# sx1509-breakout.net
KiCad netlist of a schematic drawn in EAGLE
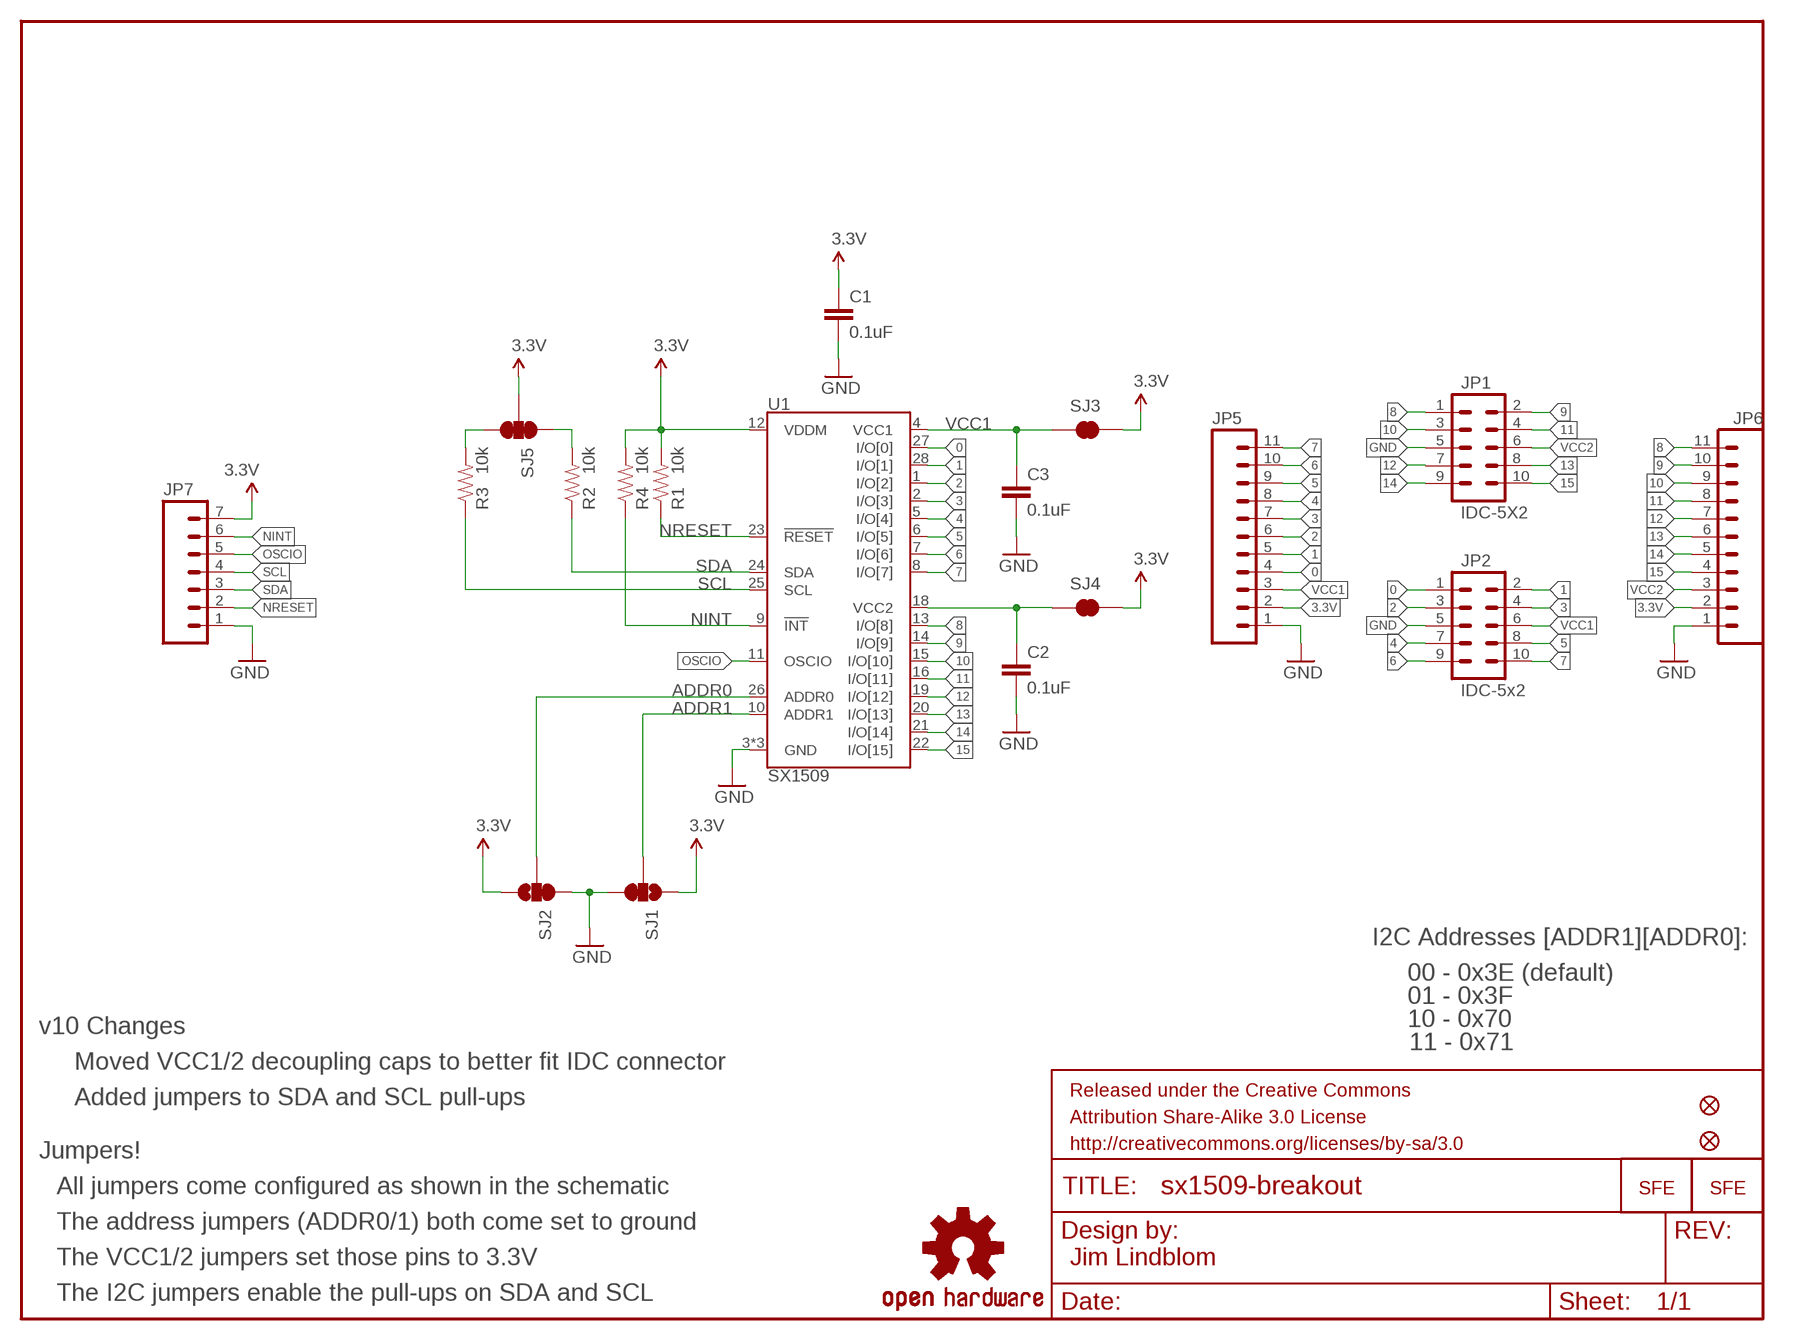
[diagram p0: schematic, sheet 1]

(export (version "E")
  (design (tool "Eeschema 10.0.6"))
  (components
    (comp (ref "C1")
      (value "0.1uF")
      (footprint "eagle-import:0402-CAP")
      (libsource (lib "eagle-import") (part "CAP0402-CAP"))
    )
    (comp (ref "C2")
      (value "0.1uF")
      (footprint "eagle-import:0402-CAP")
      (libsource (lib "eagle-import") (part "CAP0402-CAP"))
    )
    (comp (ref "C3")
      (value "0.1uF")
      (footprint "eagle-import:0402-CAP")
      (libsource (lib "eagle-import") (part "CAP0402-CAP"))
    )
    (comp (ref "JP1")
      (value "IDC-5X2")
      (footprint "eagle-import:2X5-SHROUDED-NO_SILK")
      (libsource (lib "eagle-import") (part "M05X2SHD_NS"))
    )
    (comp (ref "JP2")
      (value "IDC-5x2")
      (footprint "eagle-import:2X5-SHROUDED-NO_SILK")
      (libsource (lib "eagle-import") (part "M05X2SHD_NS"))
    )
    (comp (ref "JP3")
      (value "LOGO-SFENEW")
      (footprint "eagle-import:SFE-NEW-WEBLOGO")
      (libsource (lib "eagle-import") (part "LOGO-SFENEW"))
    )
    (comp (ref "JP4")
      (value "LOGO-SFESK")
      (footprint "eagle-import:SFE-LOGO-FLAME")
      (libsource (lib "eagle-import") (part "LOGO-SFESK"))
    )
    (comp (ref "JP5")
      (value "M111X11_NO_SILK")
      (footprint "eagle-import:1X11_NO_SILK")
      (libsource (lib "eagle-import") (part "M111X11_NO_SILK"))
    )
    (comp (ref "JP6")
      (value "M111X11_NO_SILK")
      (footprint "eagle-import:1X11_NO_SILK")
      (libsource (lib "eagle-import") (part "M111X11_NO_SILK"))
    )
    (comp (ref "JP7")
      (value "M07")
      (footprint "eagle-import:1X07")
      (libsource (lib "eagle-import") (part "M07"))
    )
    (comp (ref "JP8")
      (value "FIDUCIALUFIDUCIAL")
      (footprint "eagle-import:MICRO-FIDUCIAL")
      (libsource (lib "eagle-import") (part "FIDUCIALUFIDUCIAL"))
    )
    (comp (ref "JP9")
      (value "FIDUCIALUFIDUCIAL")
      (footprint "eagle-import:MICRO-FIDUCIAL")
      (libsource (lib "eagle-import") (part "FIDUCIALUFIDUCIAL"))
    )
    (comp (ref "R1")
      (value "10k")
      (footprint "eagle-import:0402-RES")
      (libsource (lib "eagle-import") (part "RESISTOR0402-RES"))
    )
    (comp (ref "R2")
      (value "10k")
      (footprint "eagle-import:0402-RES")
      (libsource (lib "eagle-import") (part "RESISTOR0402-RES"))
    )
    (comp (ref "R3")
      (value "10k")
      (footprint "eagle-import:0402-RES")
      (libsource (lib "eagle-import") (part "RESISTOR0402-RES"))
    )
    (comp (ref "R4")
      (value "10k")
      (footprint "eagle-import:0402-RES")
      (libsource (lib "eagle-import") (part "RESISTOR0402-RES"))
    )
    (comp (ref "SJ1")
      (value "SOLDERJUMPER_2WAYS")
      (footprint "eagle-import:SJ_3")
      (libsource (lib "eagle-import") (part "SOLDERJUMPER_2WAYS"))
    )
    (comp (ref "SJ2")
      (value "SOLDERJUMPER_2WAYS")
      (footprint "eagle-import:SJ_3")
      (libsource (lib "eagle-import") (part "SOLDERJUMPER_2WAYS"))
    )
    (comp (ref "SJ3")
      (value "SOLDERJUMPERNO")
      (footprint "eagle-import:SJ_2S-NO")
      (libsource (lib "eagle-import") (part "SOLDERJUMPERNO"))
    )
    (comp (ref "SJ4")
      (value "SOLDERJUMPERNO")
      (footprint "eagle-import:SJ_2S-NO")
      (libsource (lib "eagle-import") (part "SOLDERJUMPERNO"))
    )
    (comp (ref "SJ5")
      (value "SOLDERJUMPER_2WAYS")
      (footprint "eagle-import:SJ_3")
      (libsource (lib "eagle-import") (part "SOLDERJUMPER_2WAYS"))
    )
    (comp (ref "U$1")
      (value "OSHW-LOGOS")
      (footprint "eagle-import:OSHW-LOGO-S")
      (libsource (lib "eagle-import") (part "OSHW-LOGOS"))
    )
    (comp (ref "U1")
      (value "SX1509")
      (footprint "eagle-import:QFN-28")
      (libsource (lib "eagle-import") (part "SX1509"))
    )
  )
  (nets
    (net (code "1") (name "/ADDR0") (class "Default")
      (node (ref "SJ2") (pin "2") (pinfunction "2_2") (pintype "passive"))
      (node (ref "U1") (pin "26") (pinfunction "ADDR0_26") (pintype "bidirectional"))
    )
    (net (code "2") (name "/ADDR1") (class "Default")
      (node (ref "SJ1") (pin "2") (pinfunction "2_2") (pintype "passive"))
      (node (ref "U1") (pin "10") (pinfunction "ADDR1_10") (pintype "bidirectional"))
    )
    (net (code "3") (name "0") (class "Default")
      (node (ref "JP2") (pin "1") (pinfunction "1_1") (pintype "passive"))
      (node (ref "JP5") (pin "4") (pinfunction "4_4") (pintype "passive"))
      (node (ref "U1") (pin "27") (pinfunction "I/O[0]_27") (pintype "bidirectional"))
    )
    (net (code "4") (name "1") (class "Default")
      (node (ref "JP2") (pin "2") (pinfunction "2_2") (pintype "passive"))
      (node (ref "JP5") (pin "5") (pinfunction "5_5") (pintype "passive"))
      (node (ref "U1") (pin "28") (pinfunction "I/O[1]_28") (pintype "bidirectional"))
    )
    (net (code "5") (name "2") (class "Default")
      (node (ref "JP2") (pin "3") (pinfunction "3_3") (pintype "passive"))
      (node (ref "JP5") (pin "6") (pinfunction "6_6") (pintype "passive"))
      (node (ref "U1") (pin "1") (pinfunction "I/O[2]_1") (pintype "bidirectional"))
    )
    (net (code "6") (name "3") (class "Default")
      (node (ref "JP2") (pin "4") (pinfunction "4_4") (pintype "passive"))
      (node (ref "JP5") (pin "7") (pinfunction "7_7") (pintype "passive"))
      (node (ref "U1") (pin "2") (pinfunction "I/O[3]_2") (pintype "bidirectional"))
    )
    (net (code "7") (name "3.3V") (class "Default")
      (node (ref "C1") (pin "1") (pinfunction "1_1") (pintype "passive"))
      (node (ref "JP5") (pin "2") (pinfunction "2_2") (pintype "passive"))
      (node (ref "JP6") (pin "2") (pinfunction "2_2") (pintype "passive"))
      (node (ref "JP7") (pin "7") (pinfunction "7_7") (pintype "passive"))
      (node (ref "R1") (pin "2") (pinfunction "2_2") (pintype "passive"))
      (node (ref "R4") (pin "2") (pinfunction "2_2") (pintype "passive"))
      (node (ref "SJ1") (pin "1") (pinfunction "1_1") (pintype "passive"))
      (node (ref "SJ2") (pin "3") (pinfunction "3_3") (pintype "passive"))
      (node (ref "SJ3") (pin "2") (pinfunction "2_2") (pintype "passive"))
      (node (ref "SJ4") (pin "2") (pinfunction "2_2") (pintype "passive"))
      (node (ref "SJ5") (pin "2") (pinfunction "2_2") (pintype "passive"))
      (node (ref "U1") (pin "12") (pinfunction "VDDM_12") (pintype "bidirectional"))
    )
    (net (code "8") (name "4") (class "Default")
      (node (ref "JP2") (pin "7") (pinfunction "7_7") (pintype "passive"))
      (node (ref "JP5") (pin "8") (pinfunction "8_8") (pintype "passive"))
      (node (ref "U1") (pin "5") (pinfunction "I/O[4]_5") (pintype "bidirectional"))
    )
    (net (code "9") (name "5") (class "Default")
      (node (ref "JP2") (pin "8") (pinfunction "8_8") (pintype "passive"))
      (node (ref "JP5") (pin "9") (pinfunction "9_9") (pintype "passive"))
      (node (ref "U1") (pin "6") (pinfunction "I/O[5]_6") (pintype "bidirectional"))
    )
    (net (code "10") (name "6") (class "Default")
      (node (ref "JP2") (pin "9") (pinfunction "9_9") (pintype "passive"))
      (node (ref "JP5") (pin "10") (pinfunction "10_10") (pintype "passive"))
      (node (ref "U1") (pin "7") (pinfunction "I/O[6]_7") (pintype "bidirectional"))
    )
    (net (code "11") (name "7") (class "Default")
      (node (ref "JP2") (pin "10") (pinfunction "10_10") (pintype "passive"))
      (node (ref "JP5") (pin "11") (pinfunction "11_11") (pintype "passive"))
      (node (ref "U1") (pin "8") (pinfunction "I/O[7]_8") (pintype "bidirectional"))
    )
    (net (code "12") (name "8") (class "Default")
      (node (ref "JP1") (pin "1") (pinfunction "1_1") (pintype "passive"))
      (node (ref "JP6") (pin "11") (pinfunction "11_11") (pintype "passive"))
      (node (ref "U1") (pin "13") (pinfunction "I/O[8]_13") (pintype "bidirectional"))
    )
    (net (code "13") (name "9") (class "Default")
      (node (ref "JP1") (pin "2") (pinfunction "2_2") (pintype "passive"))
      (node (ref "JP6") (pin "10") (pinfunction "10_10") (pintype "passive"))
      (node (ref "U1") (pin "14") (pinfunction "I/O[9]_14") (pintype "bidirectional"))
    )
    (net (code "14") (name "10") (class "Default")
      (node (ref "JP1") (pin "3") (pinfunction "3_3") (pintype "passive"))
      (node (ref "JP6") (pin "9") (pinfunction "9_9") (pintype "passive"))
      (node (ref "U1") (pin "15") (pinfunction "I/O[10]_15") (pintype "bidirectional"))
    )
    (net (code "15") (name "11") (class "Default")
      (node (ref "JP1") (pin "4") (pinfunction "4_4") (pintype "passive"))
      (node (ref "JP6") (pin "8") (pinfunction "8_8") (pintype "passive"))
      (node (ref "U1") (pin "16") (pinfunction "I/O[11]_16") (pintype "bidirectional"))
    )
    (net (code "16") (name "12") (class "Default")
      (node (ref "JP1") (pin "7") (pinfunction "7_7") (pintype "passive"))
      (node (ref "JP6") (pin "7") (pinfunction "7_7") (pintype "passive"))
      (node (ref "U1") (pin "19") (pinfunction "I/O[12]_19") (pintype "bidirectional"))
    )
    (net (code "17") (name "13") (class "Default")
      (node (ref "JP1") (pin "8") (pinfunction "8_8") (pintype "passive"))
      (node (ref "JP6") (pin "6") (pinfunction "6_6") (pintype "passive"))
      (node (ref "U1") (pin "20") (pinfunction "I/O[13]_20") (pintype "bidirectional"))
    )
    (net (code "18") (name "14") (class "Default")
      (node (ref "JP1") (pin "9") (pinfunction "9_9") (pintype "passive"))
      (node (ref "JP6") (pin "5") (pinfunction "5_5") (pintype "passive"))
      (node (ref "U1") (pin "21") (pinfunction "I/O[14]_21") (pintype "bidirectional"))
    )
    (net (code "19") (name "15") (class "Default")
      (node (ref "JP1") (pin "10") (pinfunction "10_10") (pintype "passive"))
      (node (ref "JP6") (pin "4") (pinfunction "4_4") (pintype "passive"))
      (node (ref "U1") (pin "22") (pinfunction "I/O[15]_22") (pintype "bidirectional"))
    )
    (net (code "20") (name "GND") (class "Default")
      (node (ref "C1") (pin "2") (pinfunction "2_2") (pintype "passive"))
      (node (ref "C2") (pin "2") (pinfunction "2_2") (pintype "passive"))
      (node (ref "C3") (pin "2") (pinfunction "2_2") (pintype "passive"))
      (node (ref "JP1") (pin "5") (pinfunction "5_5") (pintype "passive"))
      (node (ref "JP2") (pin "5") (pinfunction "5_5") (pintype "passive"))
      (node (ref "JP5") (pin "1") (pinfunction "1_1") (pintype "passive"))
      (node (ref "JP6") (pin "1") (pinfunction "1_1") (pintype "passive"))
      (node (ref "JP7") (pin "1") (pinfunction "1_1") (pintype "passive"))
      (node (ref "SJ1") (pin "3") (pinfunction "3_3") (pintype "passive"))
      (node (ref "SJ2") (pin "1") (pinfunction "1_1") (pintype "passive"))
      (node (ref "U1") (pin "17") (pinfunction "GND_17") (pintype "bidirectional"))
      (node (ref "U1") (pin "29") (pinfunction "GND_29") (pintype "bidirectional"))
      (node (ref "U1") (pin "3") (pinfunction "GND_3") (pintype "bidirectional"))
    )
    (net (code "21") (name "NINT") (class "Default")
      (node (ref "JP7") (pin "6") (pinfunction "6_6") (pintype "passive"))
      (node (ref "R4") (pin "1") (pinfunction "1_1") (pintype "passive"))
      (node (ref "U1") (pin "9") (pinfunction "~{INT}_9") (pintype "bidirectional"))
    )
    (net (code "22") (name "NRESET") (class "Default")
      (node (ref "JP7") (pin "2") (pinfunction "2_2") (pintype "passive"))
      (node (ref "R1") (pin "1") (pinfunction "1_1") (pintype "passive"))
      (node (ref "U1") (pin "23") (pinfunction "~{RESET}_23") (pintype "bidirectional"))
    )
    (net (code "23") (name "Net-(R2-Pad2)") (class "Default")
      (node (ref "R2") (pin "2") (pinfunction "2_2") (pintype "passive"))
      (node (ref "SJ5") (pin "1") (pinfunction "1_1") (pintype "passive"))
    )
    (net (code "24") (name "Net-(R3-Pad2)") (class "Default")
      (node (ref "R3") (pin "2") (pinfunction "2_2") (pintype "passive"))
      (node (ref "SJ5") (pin "3") (pinfunction "3_3") (pintype "passive"))
    )
    (net (code "25") (name "OSCIO") (class "Default")
      (node (ref "JP7") (pin "5") (pinfunction "5_5") (pintype "passive"))
      (node (ref "U1") (pin "11") (pinfunction "OSCIO_11") (pintype "bidirectional"))
    )
    (net (code "26") (name "SCL") (class "Default")
      (node (ref "JP7") (pin "4") (pinfunction "4_4") (pintype "passive"))
      (node (ref "R3") (pin "1") (pinfunction "1_1") (pintype "passive"))
      (node (ref "U1") (pin "25") (pinfunction "SCL_25") (pintype "bidirectional"))
    )
    (net (code "27") (name "SDA") (class "Default")
      (node (ref "JP7") (pin "3") (pinfunction "3_3") (pintype "passive"))
      (node (ref "R2") (pin "1") (pinfunction "1_1") (pintype "passive"))
      (node (ref "U1") (pin "24") (pinfunction "SDA_24") (pintype "bidirectional"))
    )
    (net (code "28") (name "VCC1") (class "Default")
      (node (ref "C3") (pin "1") (pinfunction "1_1") (pintype "passive"))
      (node (ref "JP2") (pin "6") (pinfunction "6_6") (pintype "passive"))
      (node (ref "JP5") (pin "3") (pinfunction "3_3") (pintype "passive"))
      (node (ref "SJ3") (pin "1") (pinfunction "1_1") (pintype "passive"))
      (node (ref "U1") (pin "4") (pinfunction "VCC1_4") (pintype "bidirectional"))
    )
    (net (code "29") (name "VCC2") (class "Default")
      (node (ref "C2") (pin "1") (pinfunction "1_1") (pintype "passive"))
      (node (ref "JP1") (pin "6") (pinfunction "6_6") (pintype "passive"))
      (node (ref "JP6") (pin "3") (pinfunction "3_3") (pintype "passive"))
      (node (ref "SJ4") (pin "1") (pinfunction "1_1") (pintype "passive"))
      (node (ref "U1") (pin "18") (pinfunction "VCC2_18") (pintype "bidirectional"))
    )
  )
)
